# HomeAutomation_ESP.net
KiCad netlist of a schematic drawn in EAGLE
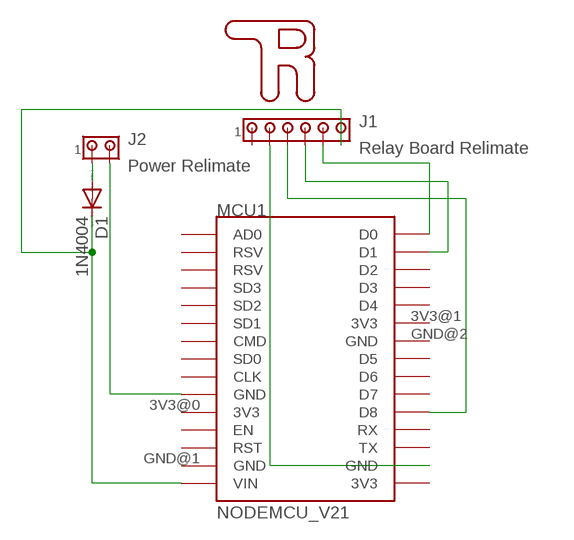
[diagram p0: schematic, sheet 1]

(export (version "E")
  (design (tool "Eeschema 10.0.6"))
  (components
    (comp (ref "D1")
      (value "1N4004")
      (footprint "eagle-import:DO41-10")
      (libsource (lib "eagle-import") (part "1N4004"))
    )
    (comp (ref "J1")
      (value "Relay Board Relimate")
      (footprint "eagle-import:10X06MTA")
      (libsource (lib "eagle-import") (part "MTA06-100"))
    )
    (comp (ref "J2")
      (value "Power Relimate")
      (footprint "eagle-import:10X02MTA")
      (libsource (lib "eagle-import") (part "MTA02-100"))
    )
    (comp (ref "MCU1")
      (value "NODEMCU_V21")
      (footprint "eagle-import:NODEMCU_NOSILK")
      (libsource (lib "eagle-import") (part "NODEMCU_V21"))
    )
    (comp (ref "U$1")
      (value "TRLOGO2")
      (footprint "eagle-import:TRLOGO_6.4")
      (libsource (lib "eagle-import") (part "TRLOGO2"))
    )
  )
  (nets
    (net (code "1") (name "Net-(D1-PadA)") (class "Default")
      (node (ref "D1") (pin "A") (pinfunction "A_A") (pintype "passive"))
      (node (ref "J2") (pin "1") (pinfunction "1_1") (pintype "passive"))
    )
    (net (code "2") (name "Net-(D1-PadC)") (class "Default")
      (node (ref "D1") (pin "C") (pinfunction "C_C") (pintype "passive"))
      (node (ref "J1") (pin "6") (pinfunction "6_6") (pintype "passive"))
      (node (ref "MCU1") (pin "VIN") (pinfunction "VIN_VIN") (pintype "bidirectional"))
    )
    (net (code "3") (name "Net-(J1-Pad2)") (class "Default")
      (node (ref "J1") (pin "2") (pinfunction "2_2") (pintype "passive"))
      (node (ref "MCU1") (pin "GND@3") (pinfunction "GND_GND@3") (pintype "bidirectional"))
    )
    (net (code "4") (name "Net-(J1-Pad3)") (class "Default")
      (node (ref "J1") (pin "3") (pinfunction "3_3") (pintype "passive"))
      (node (ref "MCU1") (pin "D8") (pinfunction "D8_D8") (pintype "bidirectional"))
    )
    (net (code "5") (name "Net-(J1-Pad4)") (class "Default")
      (node (ref "J1") (pin "4") (pinfunction "4_4") (pintype "passive"))
      (node (ref "MCU1") (pin "D1") (pinfunction "D1_D1") (pintype "bidirectional"))
    )
    (net (code "6") (name "Net-(J1-Pad5)") (class "Default")
      (node (ref "J1") (pin "5") (pinfunction "5_5") (pintype "passive"))
      (node (ref "MCU1") (pin "D0") (pinfunction "D0_D0") (pintype "bidirectional"))
    )
    (net (code "7") (name "Net-(J2-Pad2)") (class "Default")
      (node (ref "J2") (pin "2") (pinfunction "2_2") (pintype "passive"))
      (node (ref "MCU1") (pin "GND@0") (pinfunction "GND_GND@0") (pintype "bidirectional"))
    )
    (net (code "8") (name "unconnected-(J1-Pad1)") (class "Default")
      (node (ref "J1") (pin "1") (pinfunction "1_1") (pintype "passive"))
    )
    (net (code "9") (name "unconnected-(MCU1-3V3-Pad3V3@0)") (class "Default")
      (node (ref "MCU1") (pin "3V3@0") (pinfunction "3V3_3V3@0") (pintype "bidirectional"))
    )
    (net (code "10") (name "unconnected-(MCU1-3V3-Pad3V3@1)") (class "Default")
      (node (ref "MCU1") (pin "3V3@1") (pinfunction "3V3_3V3@1") (pintype "bidirectional"))
    )
    (net (code "11") (name "unconnected-(MCU1-3V3-Pad3V3@2)") (class "Default")
      (node (ref "MCU1") (pin "3V3@2") (pinfunction "3V3_3V3@2") (pintype "bidirectional"))
    )
    (net (code "12") (name "unconnected-(MCU1-GND-PadGND@1)") (class "Default")
      (node (ref "MCU1") (pin "GND@1") (pinfunction "GND_GND@1") (pintype "bidirectional"))
    )
    (net (code "13") (name "unconnected-(MCU1-GND-PadGND@2)") (class "Default")
      (node (ref "MCU1") (pin "GND@2") (pinfunction "GND_GND@2") (pintype "bidirectional"))
    )
    (net (code "14") (name "unconnected-(MCU1-PadAD0)") (class "Default")
      (node (ref "MCU1") (pin "AD0") (pinfunction "AD0_AD0") (pintype "bidirectional"))
    )
    (net (code "15") (name "unconnected-(MCU1-PadCLK)") (class "Default")
      (node (ref "MCU1") (pin "CLK") (pinfunction "CLK_CLK") (pintype "bidirectional"))
    )
    (net (code "16") (name "unconnected-(MCU1-PadCMD)") (class "Default")
      (node (ref "MCU1") (pin "CMD") (pinfunction "CMD_CMD") (pintype "bidirectional"))
    )
    (net (code "17") (name "unconnected-(MCU1-PadD2)") (class "Default")
      (node (ref "MCU1") (pin "D2") (pinfunction "D2_D2") (pintype "bidirectional"))
    )
    (net (code "18") (name "unconnected-(MCU1-PadD3)") (class "Default")
      (node (ref "MCU1") (pin "D3") (pinfunction "D3_D3") (pintype "bidirectional"))
    )
    (net (code "19") (name "unconnected-(MCU1-PadD4)") (class "Default")
      (node (ref "MCU1") (pin "D4") (pinfunction "D4_D4") (pintype "bidirectional"))
    )
    (net (code "20") (name "unconnected-(MCU1-PadD5)") (class "Default")
      (node (ref "MCU1") (pin "D5") (pinfunction "D5_D5") (pintype "bidirectional"))
    )
    (net (code "21") (name "unconnected-(MCU1-PadD6)") (class "Default")
      (node (ref "MCU1") (pin "D6") (pinfunction "D6_D6") (pintype "bidirectional"))
    )
    (net (code "22") (name "unconnected-(MCU1-PadD7)") (class "Default")
      (node (ref "MCU1") (pin "D7") (pinfunction "D7_D7") (pintype "bidirectional"))
    )
    (net (code "23") (name "unconnected-(MCU1-PadEN)") (class "Default")
      (node (ref "MCU1") (pin "EN") (pinfunction "EN_EN") (pintype "bidirectional"))
    )
    (net (code "24") (name "unconnected-(MCU1-PadRST)") (class "Default")
      (node (ref "MCU1") (pin "RST") (pinfunction "RST_RST") (pintype "bidirectional"))
    )
    (net (code "25") (name "unconnected-(MCU1-PadRX)") (class "Default")
      (node (ref "MCU1") (pin "RX") (pinfunction "RX_RX") (pintype "bidirectional"))
    )
    (net (code "26") (name "unconnected-(MCU1-PadSD0)") (class "Default")
      (node (ref "MCU1") (pin "SD0") (pinfunction "SD0_SD0") (pintype "bidirectional"))
    )
    (net (code "27") (name "unconnected-(MCU1-PadSD1)") (class "Default")
      (node (ref "MCU1") (pin "SD1") (pinfunction "SD1_SD1") (pintype "bidirectional"))
    )
    (net (code "28") (name "unconnected-(MCU1-PadSD2)") (class "Default")
      (node (ref "MCU1") (pin "SD2") (pinfunction "SD2_SD2") (pintype "bidirectional"))
    )
    (net (code "29") (name "unconnected-(MCU1-PadSD3)") (class "Default")
      (node (ref "MCU1") (pin "SD3") (pinfunction "SD3_SD3") (pintype "bidirectional"))
    )
    (net (code "30") (name "unconnected-(MCU1-PadTX)") (class "Default")
      (node (ref "MCU1") (pin "TX") (pinfunction "TX_TX") (pintype "bidirectional"))
    )
    (net (code "31") (name "unconnected-(MCU1-RSV-PadRSV@0)") (class "Default")
      (node (ref "MCU1") (pin "RSV@0") (pinfunction "RSV_RSV@0") (pintype "bidirectional"))
    )
    (net (code "32") (name "unconnected-(MCU1-RSV-PadRSV@1)") (class "Default")
      (node (ref "MCU1") (pin "RSV@1") (pinfunction "RSV_RSV@1") (pintype "bidirectional"))
    )
  )
)
